# mapleCUx_large_401-014-not-produced.net
KiCad netlist of a schematic drawn in EAGLE
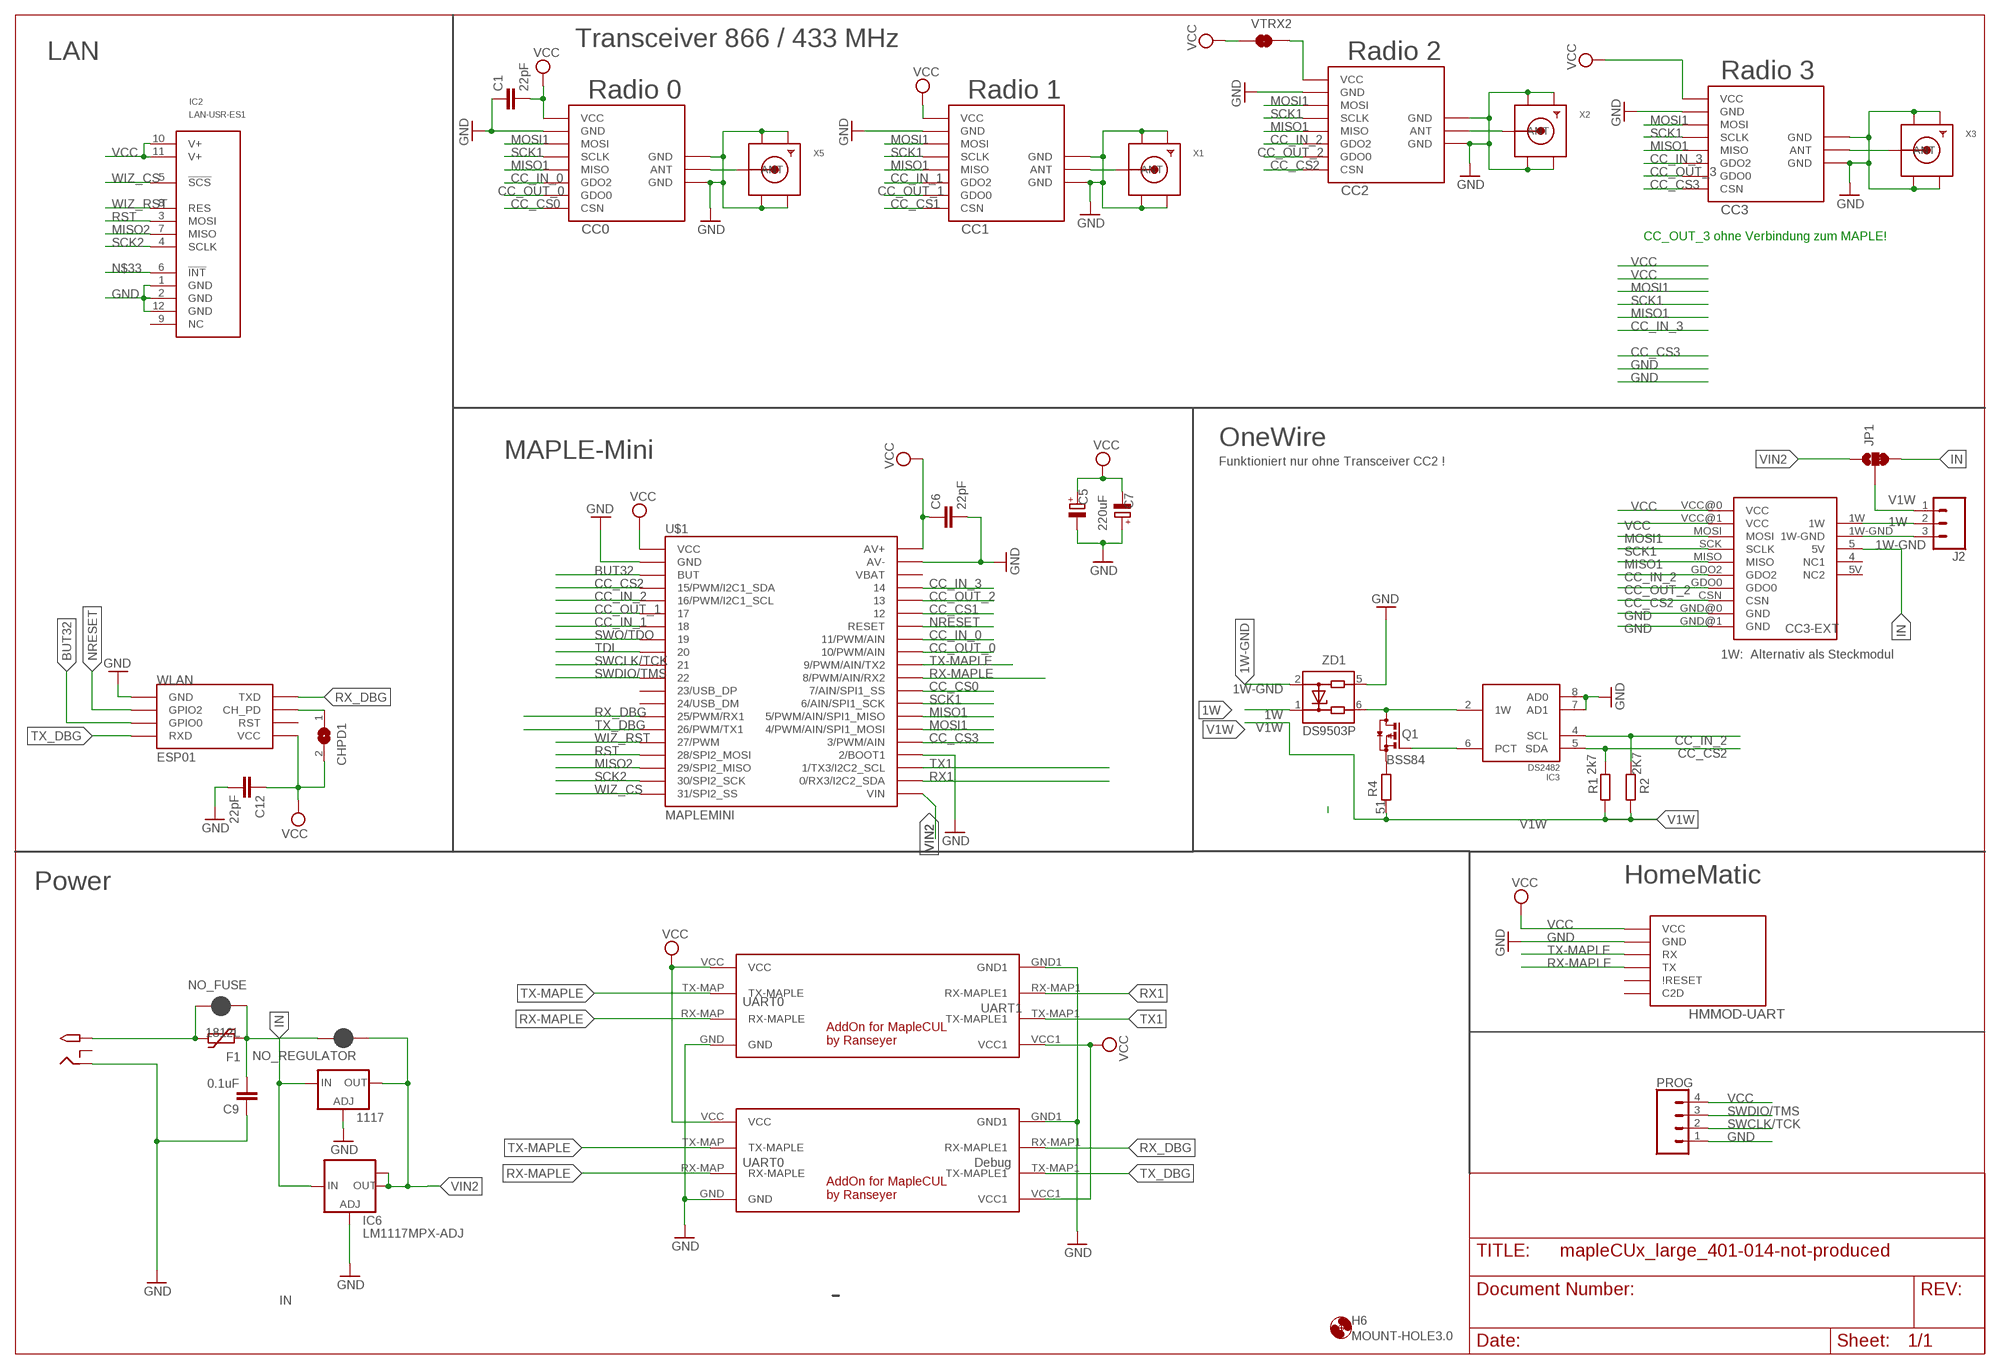
[diagram p0: schematic, sheet 1]

(export (version "E")
  (design (tool "Eeschema 10.0.6"))
  (components
    (comp (ref "1117")
      (value "LD117ADT50TR")
      (footprint "eagle-import:DPACK")
      (libsource (lib "eagle-import") (part "LD117A?DT50TR"))
    )
    (comp (ref "C1")
      (value "22pF")
      (footprint "eagle-import:C0805")
      (libsource (lib "eagle-import") (part "C-EUC0805"))
    )
    (comp (ref "C5")
      (value "220uF")
      (footprint "eagle-import:E5-8,5")
      (libsource (lib "eagle-import") (part "CPOL-EUE5-8.5"))
    )
    (comp (ref "C6")
      (value "22pF")
      (footprint "eagle-import:C0805")
      (libsource (lib "eagle-import") (part "C-EUC0805"))
    )
    (comp (ref "C7")
      (value "CPOL-EUSMCE")
      (footprint "eagle-import:SMC_E")
      (libsource (lib "eagle-import") (part "rcl_334_CPOL-EUSMCE"))
    )
    (comp (ref "C9")
      (value "0.1uF")
      (footprint "eagle-import:C1206")
      (libsource (lib "eagle-import") (part "C-EUC1206"))
    )
    (comp (ref "C12")
      (value "22pF")
      (footprint "eagle-import:C0805")
      (libsource (lib "eagle-import") (part "C-EUC0805"))
    )
    (comp (ref "CC0")
      (value "CC1101")
      (footprint "eagle-import:CC1101_MODULE1_SMD")
      (libsource (lib "eagle-import") (part "CC1101_MODULE1SMD"))
    )
    (comp (ref "CC1")
      (value "CC1101_MODULE1SMD")
      (footprint "eagle-import:CC1101_MODULE1_SMD")
      (libsource (lib "eagle-import") (part "CC1101_MODULE1SMD"))
    )
    (comp (ref "CC2")
      (value "CC1101_MODULE1SMD")
      (footprint "eagle-import:CC1101_MODULE1_SMD")
      (libsource (lib "eagle-import") (part "CC1101_MODULE1SMD"))
    )
    (comp (ref "CC3")
      (value "CC1101_MODULE1SMD")
      (footprint "eagle-import:CC1101_MODULE1_SMD")
      (libsource (lib "eagle-import") (part "CC1101_MODULE1SMD"))
    )
    (comp (ref "CC3-EXT")
      (value "ONEWIRE-MODULE")
      (footprint "eagle-import:ONEWIRE_CC1101_MODULE3_DIL")
      (libsource (lib "eagle-import") (part "ONEWIRE-MODULE"))
    )
    (comp (ref "CHPD1")
      (value "SJ")
      (footprint "eagle-import:SJ")
      (libsource (lib "eagle-import") (part "SJ"))
    )
    (comp (ref "F1")
      (value "1812L")
      (footprint "eagle-import:1812L")
      (libsource (lib "eagle-import") (part "1812L"))
    )
    (comp (ref "H6")
      (value "MOUNT-HOLE3.0")
      (footprint "eagle-import:3,0")
      (libsource (lib "eagle-import") (part "MOUNT-HOLE3.0"))
    )
    (comp (ref "HMMOD-UART")
      (value "HM-MOD-UARTDIL")
      (footprint "eagle-import:HM-MOD-UART-DIL")
      (libsource (lib "eagle-import") (part "HM-MOD-UARTDIL"))
    )
    (comp (ref "IC2")
      (value "LAN-USR-ES1")
      (footprint "eagle-import:USR-ES1")
      (libsource (lib "eagle-import") (part "LAN-USR-ES1"))
    )
    (comp (ref "IC3")
      (value "DS2482")
      (footprint "eagle-import:SO08")
      (libsource (lib "eagle-import") (part "DS2482-100S"))
    )
    (comp (ref "IC6")
      (value "LM1117MPX-ADJ")
      (footprint "eagle-import:SOT223")
      (libsource (lib "eagle-import") (part "LM1117MPX-ADJ"))
    )
    (comp (ref "J2")
      (value "CONN_03LONGPADS")
      (footprint "eagle-import:1X03_LONGPADS")
      (libsource (lib "eagle-import") (part "CONN_03LONGPADS"))
    )
    (comp (ref "JP1")
      (value "JUMPER-SMT_3_1-NC_TRACE_SILK")
      (footprint "eagle-import:SMT-JUMPER_3_1-NC_TRACE_SILK")
      (libsource (lib "eagle-import") (part "JUMPER-SMT_3_1-NC_TRACE_SILK"))
    )
    (comp (ref "NO_FUSE")
      (value "JUMPER-SMT_2_NC_PASTE_NO-SILK")
      (footprint "eagle-import:SMT-JUMPER_2_NC_PASTE_NO-SILK")
      (libsource (lib "eagle-import") (part "JUMPER-SMT_2_NC_PASTE_NO-SILK"))
    )
    (comp (ref "NO_REGULATOR")
      (value "JUMPER-SMT_2_NC_PASTE_NO-SILK")
      (footprint "eagle-import:SMT-JUMPER_2_NC_PASTE_NO-SILK")
      (libsource (lib "eagle-import") (part "JUMPER-SMT_2_NC_PASTE_NO-SILK"))
    )
    (comp (ref "PROG")
      (value "CONN_04LOCK")
      (footprint "eagle-import:1X04_LOCK")
      (libsource (lib "eagle-import") (part "CONN_04LOCK"))
    )
    (comp (ref "Q1")
      (value "BSS84")
      (footprint "eagle-import:SOT23")
      (libsource (lib "eagle-import") (part "BSS84"))
    )
    (comp (ref "R1")
      (value "2k7")
      (footprint "eagle-import:R0805")
      (libsource (lib "eagle-import") (part "R-EU_R0805"))
    )
    (comp (ref "R2")
      (value "2K7")
      (footprint "eagle-import:R0805")
      (libsource (lib "eagle-import") (part "R-EU_R0805"))
    )
    (comp (ref "R4")
      (value "51")
      (footprint "eagle-import:R0805")
      (libsource (lib "eagle-import") (part "R-EU_R0805"))
    )
    (comp (ref "U$1")
      (value "MAPLEMINI")
      (footprint "eagle-import:20-DIP")
      (libsource (lib "eagle-import") (part "MAPLEMINI"))
    )
    (comp (ref "U$2")
      (value "2.1MMJACKTHM")
      (footprint "eagle-import:PJ-102A")
      (libsource (lib "eagle-import") (part "2.1MMJACKTHM"))
    )
    (comp (ref "U$3")
      (value "MAPLE-CUL-ADDON-V01")
      (footprint "eagle-import:MAPLE-CUL-V01")
      (libsource (lib "eagle-import") (part "MAPLE-CUL-ADDON-V01"))
    )
    (comp (ref "U$4")
      (value "MAPLE-CUL-ADDON-V01")
      (footprint "eagle-import:MAPLE-CUL-V01")
      (libsource (lib "eagle-import") (part "MAPLE-CUL-ADDON-V01"))
    )
    (comp (ref "VTRX2")
      (value "JUMPER-SMT_2_NC_TRACE_SILK")
      (footprint "eagle-import:SMT-JUMPER_2_NC_TRACE_SILK")
      (libsource (lib "eagle-import") (part "JUMPER-SMT_2_NC_TRACE_SILK"))
    )
    (comp (ref "WLAN")
      (value "ESP01")
      (footprint "eagle-import:ESP01")
      (libsource (lib "eagle-import") (part "ESP01"))
    )
    (comp (ref "X1")
      (value "SMACONNECTOR_EDGE")
      (footprint "eagle-import:SMA_EDGELAUNCH")
      (libsource (lib "eagle-import") (part "SMACONNECTOR_EDGE"))
    )
    (comp (ref "X2")
      (value "SMACONNECTOR_EDGE")
      (footprint "eagle-import:SMA_EDGELAUNCH")
      (libsource (lib "eagle-import") (part "SMACONNECTOR_EDGE"))
    )
    (comp (ref "X3")
      (value "SMACONNECTOR_EDGE")
      (footprint "eagle-import:SMA_EDGELAUNCH")
      (libsource (lib "eagle-import") (part "SMACONNECTOR_EDGE"))
    )
    (comp (ref "X5")
      (value "SMACONNECTOR_EDGE")
      (footprint "eagle-import:SMA_EDGELAUNCH")
      (libsource (lib "eagle-import") (part "SMACONNECTOR_EDGE"))
    )
    (comp (ref "ZD1")
      (value "DS9503P")
      (footprint "eagle-import:TSOC6")
      (libsource (lib "eagle-import") (part "DS9503P"))
    )
  )
  (nets
    (net (code "1") (name "/CC_CS0") (class "Default")
      (node (ref "CC0") (pin "CSN") (pinfunction "CSN_CSN") (pintype "bidirectional"))
      (node (ref "U$1") (pin "29") (pinfunction "7/AIN/SPI1_SS_29") (pintype "bidirectional"))
    )
    (net (code "2") (name "/CC_CS1") (class "Default")
      (node (ref "CC1") (pin "CSN") (pinfunction "CSN_CSN") (pintype "bidirectional"))
      (node (ref "U$1") (pin "35") (pinfunction "12_35") (pintype "bidirectional"))
    )
    (net (code "3") (name "/CC_CS2") (class "Default")
      (node (ref "CC2") (pin "CSN") (pinfunction "CSN_CSN") (pintype "bidirectional"))
      (node (ref "CC3-EXT") (pin "CSN") (pinfunction "CSN_CSN") (pintype "bidirectional"))
      (node (ref "IC3") (pin "5") (pinfunction "SDA_5") (pintype "bidirectional"))
      (node (ref "R1") (pin "2") (pinfunction "2_2") (pintype "passive"))
      (node (ref "U$1") (pin "4") (pinfunction "15/PWM/I2C1_SDA_4") (pintype "bidirectional"))
    )
    (net (code "4") (name "/CC_CS3") (class "Default")
      (node (ref "CC3") (pin "CSN") (pinfunction "CSN_CSN") (pintype "bidirectional"))
      (node (ref "U$1") (pin "25") (pinfunction "3/PWM/AIN_25") (pintype "bidirectional"))
    )
    (net (code "5") (name "/CC_IN_0") (class "Default")
      (node (ref "CC0") (pin "GDO2") (pinfunction "GDO2_GDO2") (pintype "bidirectional"))
      (node (ref "U$1") (pin "33") (pinfunction "11/PWM/AIN_33") (pintype "bidirectional"))
    )
    (net (code "6") (name "/CC_IN_1") (class "Default")
      (node (ref "CC1") (pin "GDO2") (pinfunction "GDO2_GDO2") (pintype "bidirectional"))
      (node (ref "U$1") (pin "7") (pinfunction "18_7") (pintype "bidirectional"))
    )
    (net (code "7") (name "/CC_IN_2") (class "Default")
      (node (ref "CC2") (pin "GDO2") (pinfunction "GDO2_GDO2") (pintype "bidirectional"))
      (node (ref "CC3-EXT") (pin "GDO2") (pinfunction "GDO2_GDO2") (pintype "bidirectional"))
      (node (ref "IC3") (pin "4") (pinfunction "SCL_4") (pintype "input"))
      (node (ref "R2") (pin "2") (pinfunction "2_2") (pintype "passive"))
      (node (ref "U$1") (pin "5") (pinfunction "16/PWM/I2C1_SCL_5") (pintype "bidirectional"))
    )
    (net (code "8") (name "/CC_IN_3") (class "Default")
      (node (ref "CC3") (pin "GDO2") (pinfunction "GDO2_GDO2") (pintype "bidirectional"))
      (node (ref "U$1") (pin "37") (pinfunction "14_37") (pintype "bidirectional"))
    )
    (net (code "9") (name "/CC_OUT_0") (class "Default")
      (node (ref "CC0") (pin "GDO0") (pinfunction "GDO0_GDO0") (pintype "bidirectional"))
      (node (ref "U$1") (pin "32") (pinfunction "10/PWM/AIN_32") (pintype "bidirectional"))
    )
    (net (code "10") (name "/CC_OUT_1") (class "Default")
      (node (ref "CC1") (pin "GDO0") (pinfunction "GDO0_GDO0") (pintype "bidirectional"))
      (node (ref "U$1") (pin "6") (pinfunction "17_6") (pintype "bidirectional"))
    )
    (net (code "11") (name "/CC_OUT_2") (class "Default")
      (node (ref "CC2") (pin "GDO0") (pinfunction "GDO0_GDO0") (pintype "bidirectional"))
      (node (ref "CC3-EXT") (pin "GDO0") (pinfunction "GDO0_GDO0") (pintype "bidirectional"))
      (node (ref "U$1") (pin "36") (pinfunction "13_36") (pintype "bidirectional"))
    )
    (net (code "12") (name "/CC_OUT_3") (class "Default")
      (node (ref "CC3") (pin "GDO0") (pinfunction "GDO0_GDO0") (pintype "bidirectional"))
    )
    (net (code "13") (name "/MISO1") (class "Default")
      (node (ref "CC0") (pin "MISO") (pinfunction "MISO_MISO") (pintype "bidirectional"))
      (node (ref "CC1") (pin "MISO") (pinfunction "MISO_MISO") (pintype "bidirectional"))
      (node (ref "CC2") (pin "MISO") (pinfunction "MISO_MISO") (pintype "bidirectional"))
      (node (ref "CC3") (pin "MISO") (pinfunction "MISO_MISO") (pintype "bidirectional"))
      (node (ref "CC3-EXT") (pin "MISO") (pinfunction "MISO_MISO") (pintype "bidirectional"))
      (node (ref "U$1") (pin "27") (pinfunction "5/PWM/AIN/SPI1_MISO_27") (pintype "bidirectional"))
    )
    (net (code "14") (name "/MISO2") (class "Default")
      (node (ref "IC2") (pin "7") (pinfunction "MISO_7") (pintype "bidirectional"))
      (node (ref "U$1") (pin "18") (pinfunction "29/SPI2_MISO_18") (pintype "bidirectional"))
    )
    (net (code "15") (name "/MOSI1") (class "Default")
      (node (ref "CC0") (pin "MOSI") (pinfunction "MOSI_MOSI") (pintype "bidirectional"))
      (node (ref "CC1") (pin "MOSI") (pinfunction "MOSI_MOSI") (pintype "bidirectional"))
      (node (ref "CC2") (pin "MOSI") (pinfunction "MOSI_MOSI") (pintype "bidirectional"))
      (node (ref "CC3") (pin "MOSI") (pinfunction "MOSI_MOSI") (pintype "bidirectional"))
      (node (ref "CC3-EXT") (pin "MOSI") (pinfunction "MOSI_MOSI") (pintype "bidirectional"))
      (node (ref "U$1") (pin "26") (pinfunction "4/PWM/AIN/SPI1_MOSI_26") (pintype "bidirectional"))
    )
    (net (code "16") (name "/N$33") (class "Default")
      (node (ref "IC2") (pin "6") (pinfunction "~{INT}_6") (pintype "output"))
    )
    (net (code "17") (name "/RST") (class "Default")
      (node (ref "IC2") (pin "3") (pinfunction "MOSI_3") (pintype "bidirectional"))
      (node (ref "U$1") (pin "17") (pinfunction "28/SPI2_MOSI_17") (pintype "bidirectional"))
    )
    (net (code "18") (name "/SCK1") (class "Default")
      (node (ref "CC0") (pin "SCLK") (pinfunction "SCLK_SCLK") (pintype "bidirectional"))
      (node (ref "CC1") (pin "SCLK") (pinfunction "SCLK_SCLK") (pintype "bidirectional"))
      (node (ref "CC2") (pin "SCLK") (pinfunction "SCLK_SCLK") (pintype "bidirectional"))
      (node (ref "CC3") (pin "SCLK") (pinfunction "SCLK_SCLK") (pintype "bidirectional"))
      (node (ref "CC3-EXT") (pin "SCK") (pinfunction "SCLK_SCK") (pintype "bidirectional"))
      (node (ref "U$1") (pin "28") (pinfunction "6/AIN/SPI1_SCK_28") (pintype "bidirectional"))
    )
    (net (code "19") (name "/SCK2") (class "Default")
      (node (ref "IC2") (pin "4") (pinfunction "SCLK_4") (pintype "input"))
      (node (ref "U$1") (pin "19") (pinfunction "30/SPI2_SCK_19") (pintype "bidirectional"))
    )
    (net (code "20") (name "/SWCLK{slash}TCK") (class "Default")
      (node (ref "PROG") (pin "2") (pinfunction "2_2") (pintype "passive"))
      (node (ref "U$1") (pin "10") (pinfunction "21_10") (pintype "bidirectional"))
    )
    (net (code "21") (name "/SWDIO{slash}TMS") (class "Default")
      (node (ref "PROG") (pin "3") (pinfunction "3_3") (pintype "passive"))
      (node (ref "U$1") (pin "11") (pinfunction "22_11") (pintype "bidirectional"))
    )
    (net (code "22") (name "/SWO{slash}TDO") (class "Default")
      (node (ref "U$1") (pin "8") (pinfunction "19_8") (pintype "bidirectional"))
    )
    (net (code "23") (name "/TDI") (class "Default")
      (node (ref "U$1") (pin "9") (pinfunction "20_9") (pintype "bidirectional"))
    )
    (net (code "24") (name "/WIZ_CS") (class "Default")
      (node (ref "IC2") (pin "5") (pinfunction "~{SCS}_5") (pintype "input"))
      (node (ref "U$1") (pin "20") (pinfunction "31/SPI2_SS_20") (pintype "bidirectional"))
    )
    (net (code "25") (name "/WIZ_RST") (class "Default")
      (node (ref "IC2") (pin "8") (pinfunction "RES_8") (pintype "input"))
      (node (ref "U$1") (pin "16") (pinfunction "27/PWM_16") (pintype "bidirectional"))
    )
    (net (code "26") (name "1W") (class "Default")
      (node (ref "CC3-EXT") (pin "1W") (pinfunction "1W_1W") (pintype "bidirectional"))
      (node (ref "J2") (pin "2") (pinfunction "2_2") (pintype "passive"))
      (node (ref "ZD1") (pin "1") (pinfunction "P$1_1") (pintype "passive"))
    )
    (net (code "27") (name "1W-GND") (class "Default")
      (node (ref "CC3-EXT") (pin "1W-GND") (pinfunction "1W-GND_1W-GND") (pintype "bidirectional"))
      (node (ref "J2") (pin "3") (pinfunction "3_3") (pintype "passive"))
      (node (ref "ZD1") (pin "2") (pinfunction "P$2_2") (pintype "passive"))
    )
    (net (code "28") (name "BUT32") (class "Default")
      (node (ref "U$1") (pin "3") (pinfunction "BUT_3") (pintype "bidirectional"))
      (node (ref "WLAN") (pin "GPIO0") (pinfunction "GPIO0_GPIO0") (pintype "bidirectional"))
    )
    (net (code "29") (name "GND") (class "Default")
      (node (ref "1117") (pin "1") (pinfunction "ADJ_1") (pintype "input"))
      (node (ref "C1") (pin "1") (pinfunction "1_1") (pintype "passive"))
      (node (ref "C12") (pin "2") (pinfunction "2_2") (pintype "passive"))
      (node (ref "C5") (pin "-") (pinfunction "-_-") (pintype "passive"))
      (node (ref "C6") (pin "2") (pinfunction "2_2") (pintype "passive"))
      (node (ref "C7") (pin "+") (pinfunction "+_+") (pintype "passive"))
      (node (ref "C9") (pin "1") (pinfunction "1_1") (pintype "passive"))
      (node (ref "CC0") (pin "GND@0") (pinfunction "GND_GND@0") (pintype "power_in"))
      (node (ref "CC0") (pin "GND@1") (pinfunction "GND_GND@1") (pintype "power_in"))
      (node (ref "CC0") (pin "GND@2") (pinfunction "GND_GND@2") (pintype "power_in"))
      (node (ref "CC1") (pin "GND@0") (pinfunction "GND_GND@0") (pintype "power_in"))
      (node (ref "CC1") (pin "GND@1") (pinfunction "GND_GND@1") (pintype "power_in"))
      (node (ref "CC1") (pin "GND@2") (pinfunction "GND_GND@2") (pintype "power_in"))
      (node (ref "CC2") (pin "GND@0") (pinfunction "GND_GND@0") (pintype "power_in"))
      (node (ref "CC2") (pin "GND@1") (pinfunction "GND_GND@1") (pintype "power_in"))
      (node (ref "CC2") (pin "GND@2") (pinfunction "GND_GND@2") (pintype "power_in"))
      (node (ref "CC3") (pin "GND@0") (pinfunction "GND_GND@0") (pintype "power_in"))
      (node (ref "CC3") (pin "GND@1") (pinfunction "GND_GND@1") (pintype "power_in"))
      (node (ref "CC3") (pin "GND@2") (pinfunction "GND_GND@2") (pintype "power_in"))
      (node (ref "CC3-EXT") (pin "GND@0") (pinfunction "GND_GND@0") (pintype "power_in"))
      (node (ref "CC3-EXT") (pin "GND@1") (pinfunction "GND_GND@1") (pintype "power_in"))
      (node (ref "HMMOD-UART") (pin "2") (pinfunction "GND_2") (pintype "power_in"))
      (node (ref "IC2") (pin "1") (pinfunction "GND_1") (pintype "power_in"))
      (node (ref "IC2") (pin "12") (pinfunction "GND_12") (pintype "power_in"))
      (node (ref "IC2") (pin "2") (pinfunction "GND_2") (pintype "power_in"))
      (node (ref "IC3") (pin "7") (pinfunction "AD1_7") (pintype "input"))
      (node (ref "IC3") (pin "8") (pinfunction "AD0_8") (pintype "input"))
      (node (ref "IC6") (pin "1") (pinfunction "ADJ_1") (pintype "input"))
      (node (ref "PROG") (pin "1") (pinfunction "1_1") (pintype "passive"))
      (node (ref "U$1") (pin "2") (pinfunction "GND_2") (pintype "bidirectional"))
      (node (ref "U$1") (pin "24") (pinfunction "2/BOOT1_24") (pintype "bidirectional"))
      (node (ref "U$1") (pin "39") (pinfunction "AV-_39") (pintype "bidirectional"))
      (node (ref "U$2") (pin "RING") (pinfunction "RING_RING") (pintype "bidirectional"))
      (node (ref "U$3") (pin "GND") (pinfunction "GND_GND") (pintype "bidirectional"))
      (node (ref "U$3") (pin "GND1") (pinfunction "GND1_GND1") (pintype "bidirectional"))
      (node (ref "U$4") (pin "GND") (pinfunction "GND_GND") (pintype "bidirectional"))
      (node (ref "U$4") (pin "GND1") (pinfunction "GND1_GND1") (pintype "bidirectional"))
      (node (ref "WLAN") (pin "GND") (pinfunction "GND_GND") (pintype "bidirectional"))
      (node (ref "X1") (pin "GND@1") (pinfunction "GND4_GND@1") (pintype "power_in"))
      (node (ref "X1") (pin "GND@2") (pinfunction "GND3_GND@2") (pintype "power_in"))
      (node (ref "X1") (pin "GND@3") (pinfunction "GND2_GND@3") (pintype "power_in"))
      (node (ref "X1") (pin "GND@4") (pinfunction "GND1_GND@4") (pintype "power_in"))
      (node (ref "X2") (pin "GND@1") (pinfunction "GND4_GND@1") (pintype "power_in"))
      (node (ref "X2") (pin "GND@2") (pinfunction "GND3_GND@2") (pintype "power_in"))
      (node (ref "X2") (pin "GND@3") (pinfunction "GND2_GND@3") (pintype "power_in"))
      (node (ref "X2") (pin "GND@4") (pinfunction "GND1_GND@4") (pintype "power_in"))
      (node (ref "X3") (pin "GND@1") (pinfunction "GND4_GND@1") (pintype "power_in"))
      (node (ref "X3") (pin "GND@2") (pinfunction "GND3_GND@2") (pintype "power_in"))
      (node (ref "X3") (pin "GND@3") (pinfunction "GND2_GND@3") (pintype "power_in"))
      (node (ref "X3") (pin "GND@4") (pinfunction "GND1_GND@4") (pintype "power_in"))
      (node (ref "X5") (pin "GND@1") (pinfunction "GND4_GND@1") (pintype "power_in"))
      (node (ref "X5") (pin "GND@2") (pinfunction "GND3_GND@2") (pintype "power_in"))
      (node (ref "X5") (pin "GND@3") (pinfunction "GND2_GND@3") (pintype "power_in"))
      (node (ref "X5") (pin "GND@4") (pinfunction "GND1_GND@4") (pintype "power_in"))
      (node (ref "ZD1") (pin "5") (pinfunction "P$3_5") (pintype "passive"))
    )
    (net (code "30") (name "IN") (class "Default")
      (node (ref "1117") (pin "3") (pinfunction "IN_3") (pintype "input"))
      (node (ref "C9") (pin "2") (pinfunction "2_2") (pintype "passive"))
      (node (ref "CC3-EXT") (pin "5") (pinfunction "5V_5") (pintype "bidirectional"))
      (node (ref "F1") (pin "P$1") (pinfunction "1_P$1") (pintype "passive"))
      (node (ref "IC6") (pin "3") (pinfunction "IN_3") (pintype "input"))
      (node (ref "JP1") (pin "3") (pinfunction "3_3") (pintype "passive"))
      (node (ref "NO_FUSE") (pin "1") (pinfunction "1_1") (pintype "passive"))
      (node (ref "NO_REGULATOR") (pin "2") (pinfunction "2_2") (pintype "passive"))
    )
    (net (code "31") (name "NRESET") (class "Default")
      (node (ref "U$1") (pin "34") (pinfunction "RESET_34") (pintype "bidirectional"))
      (node (ref "WLAN") (pin "GPIO2") (pinfunction "GPIO2_GPIO2") (pintype "bidirectional"))
    )
    (net (code "32") (name "Net-(CC2-PadVCC)") (class "Default")
      (node (ref "CC2") (pin "VCC") (pinfunction "VCC_VCC") (pintype "power_in"))
      (node (ref "VTRX2") (pin "2") (pinfunction "2_2") (pintype "passive"))
    )
    (net (code "33") (name "Net-(CHPD1-Pad1)") (class "Default")
      (node (ref "CHPD1") (pin "1") (pinfunction "1_1") (pintype "passive"))
      (node (ref "WLAN") (pin "CH_PD") (pinfunction "CH_PD_CH_PD") (pintype "bidirectional"))
    )
    (net (code "34") (name "Net-(F1-2)") (class "Default")
      (node (ref "F1") (pin "P$2") (pinfunction "2_P$2") (pintype "passive"))
      (node (ref "NO_FUSE") (pin "2") (pinfunction "2_2") (pintype "passive"))
      (node (ref "U$2") (pin "TIP") (pinfunction "TIP_TIP") (pintype "bidirectional"))
    )
    (net (code "35") (name "Net-(IC3A-1W)") (class "Default")
      (node (ref "IC3") (pin "2") (pinfunction "1W_2") (pintype "open_collector"))
      (node (ref "Q1") (pin "3") (pinfunction "D_3") (pintype "passive"))
      (node (ref "ZD1") (pin "6") (pinfunction "P$4_6") (pintype "passive"))
    )
    (net (code "36") (name "Net-(IC3A-PCT)") (class "Default")
      (node (ref "IC3") (pin "6") (pinfunction "PCT_6") (pintype "output"))
      (node (ref "Q1") (pin "1") (pinfunction "G_1") (pintype "passive"))
    )
    (net (code "37") (name "Net-(Q1-S)") (class "Default")
      (node (ref "Q1") (pin "2") (pinfunction "S_2") (pintype "passive"))
      (node (ref "R4") (pin "1") (pinfunction "1_1") (pintype "passive"))
    )
    (net (code "38") (name "Net-(X1-ANT)") (class "Default")
      (node (ref "CC1") (pin "ANT") (pinfunction "ANT_ANT") (pintype "output"))
      (node (ref "X1") (pin "P") (pinfunction "ANT_P") (pintype "bidirectional"))
    )
    (net (code "39") (name "Net-(X2-ANT)") (class "Default")
      (node (ref "CC2") (pin "ANT") (pinfunction "ANT_ANT") (pintype "output"))
      (node (ref "X2") (pin "P") (pinfunction "ANT_P") (pintype "bidirectional"))
    )
    (net (code "40") (name "Net-(X3-ANT)") (class "Default")
      (node (ref "CC3") (pin "ANT") (pinfunction "ANT_ANT") (pintype "output"))
      (node (ref "X3") (pin "P") (pinfunction "ANT_P") (pintype "bidirectional"))
    )
    (net (code "41") (name "Net-(X5-ANT)") (class "Default")
      (node (ref "CC0") (pin "ANT") (pinfunction "ANT_ANT") (pintype "output"))
      (node (ref "X5") (pin "P") (pinfunction "ANT_P") (pintype "bidirectional"))
    )
    (net (code "42") (name "RX-MAPLE") (class "Default")
      (node (ref "HMMOD-UART") (pin "5") (pinfunction "TX_5") (pintype "bidirectional"))
      (node (ref "U$1") (pin "30") (pinfunction "8/PWM/AIN/RX2_30") (pintype "bidirectional"))
      (node (ref "U$3") (pin "RX-MAP") (pinfunction "RX-MAPLE_RX-MAP") (pintype "bidirectional"))
      (node (ref "U$4") (pin "RX-MAP") (pinfunction "RX-MAPLE_RX-MAP") (pintype "bidirectional"))
    )
    (net (code "43") (name "RX1") (class "Default")
      (node (ref "U$1") (pin "22") (pinfunction "0/RX3/I2C2_SDA_22") (pintype "bidirectional"))
      (node (ref "U$3") (pin "RX-MAP1") (pinfunction "RX-MAPLE1_RX-MAP1") (pintype "bidirectional"))
    )
    (net (code "44") (name "RX_DBG") (class "Default")
      (node (ref "U$1") (pin "14") (pinfunction "25/PWM/RX1_14") (pintype "bidirectional"))
      (node (ref "U$4") (pin "RX-MAP1") (pinfunction "RX-MAPLE1_RX-MAP1") (pintype "bidirectional"))
      (node (ref "WLAN") (pin "TX") (pinfunction "TXD_TX") (pintype "bidirectional"))
    )
    (net (code "45") (name "TX-MAPLE") (class "Default")
      (node (ref "HMMOD-UART") (pin "6") (pinfunction "RX_6") (pintype "bidirectional"))
      (node (ref "U$1") (pin "31") (pinfunction "9/PWM/AIN/TX2_31") (pintype "bidirectional"))
      (node (ref "U$3") (pin "TX-MAP") (pinfunction "TX-MAPLE_TX-MAP") (pintype "bidirectional"))
      (node (ref "U$4") (pin "TX-MAP") (pinfunction "TX-MAPLE_TX-MAP") (pintype "bidirectional"))
    )
    (net (code "46") (name "TX1") (class "Default")
      (node (ref "U$1") (pin "23") (pinfunction "1/TX3/I2C2_SCL_23") (pintype "bidirectional"))
      (node (ref "U$3") (pin "TX-MAP1") (pinfunction "TX-MAPLE1_TX-MAP1") (pintype "bidirectional"))
    )
    (net (code "47") (name "TX_DBG") (class "Default")
      (node (ref "U$1") (pin "15") (pinfunction "26/PWM/TX1_15") (pintype "bidirectional"))
      (node (ref "U$4") (pin "TX-MAP1") (pinfunction "TX-MAPLE1_TX-MAP1") (pintype "bidirectional"))
      (node (ref "WLAN") (pin "RX") (pinfunction "RXD_RX") (pintype "bidirectional"))
    )
    (net (code "48") (name "V1W") (class "Default")
      (node (ref "J2") (pin "1") (pinfunction "1_1") (pintype "passive"))
      (node (ref "JP1") (pin "2") (pinfunction "2_2") (pintype "passive"))
      (node (ref "R1") (pin "1") (pinfunction "1_1") (pintype "passive"))
      (node (ref "R2") (pin "1") (pinfunction "1_1") (pintype "passive"))
      (node (ref "R4") (pin "2") (pinfunction "2_2") (pintype "passive"))
    )
    (net (code "49") (name "VCC") (class "Default")
      (node (ref "C1") (pin "2") (pinfunction "2_2") (pintype "passive"))
      (node (ref "C12") (pin "1") (pinfunction "1_1") (pintype "passive"))
      (node (ref "C5") (pin "+") (pinfunction "+_+") (pintype "passive"))
      (node (ref "C6") (pin "1") (pinfunction "1_1") (pintype "passive"))
      (node (ref "C7") (pin "-") (pinfunction "-_-") (pintype "passive"))
      (node (ref "CC0") (pin "VCC") (pinfunction "VCC_VCC") (pintype "power_in"))
      (node (ref "CC1") (pin "VCC") (pinfunction "VCC_VCC") (pintype "power_in"))
      (node (ref "CC3") (pin "VCC") (pinfunction "VCC_VCC") (pintype "power_in"))
      (node (ref "CC3-EXT") (pin "VCC@0") (pinfunction "VCC_VCC@0") (pintype "power_in"))
      (node (ref "CC3-EXT") (pin "VCC@1") (pinfunction "VCC_VCC@1") (pintype "power_in"))
      (node (ref "CHPD1") (pin "2") (pinfunction "2_2") (pintype "passive"))
      (node (ref "HMMOD-UART") (pin "1") (pinfunction "VCC_1") (pintype "power_in"))
      (node (ref "IC2") (pin "10") (pinfunction "V+_10") (pintype "power_in"))
      (node (ref "IC2") (pin "11") (pinfunction "V+_11") (pintype "power_in"))
      (node (ref "PROG") (pin "4") (pinfunction "4_4") (pintype "passive"))
      (node (ref "U$1") (pin "1") (pinfunction "VCC_1") (pintype "bidirectional"))
      (node (ref "U$1") (pin "40") (pinfunction "AV+_40") (pintype "bidirectional"))
      (node (ref "U$3") (pin "VCC") (pinfunction "VCC_VCC") (pintype "bidirectional"))
      (node (ref "U$3") (pin "VCC1") (pinfunction "VCC1_VCC1") (pintype "bidirectional"))
      (node (ref "U$4") (pin "VCC") (pinfunction "VCC_VCC") (pintype "bidirectional"))
      (node (ref "U$4") (pin "VCC1") (pinfunction "VCC1_VCC1") (pintype "bidirectional"))
      (node (ref "VTRX2") (pin "1") (pinfunction "1_1") (pintype "passive"))
      (node (ref "WLAN") (pin "VCC") (pinfunction "VCC_VCC") (pintype "bidirectional"))
    )
    (net (code "50") (name "VIN2") (class "Default")
      (node (ref "1117") (pin "4") (pinfunction "OUT_4") (pintype "passive"))
      (node (ref "IC6") (pin "2") (pinfunction "OUT_2") (pintype "passive"))
      (node (ref "IC6") (pin "TAB") (pinfunction "OUT1_TAB") (pintype "passive"))
      (node (ref "JP1") (pin "1") (pinfunction "1_1") (pintype "passive"))
      (node (ref "NO_REGULATOR") (pin "1") (pinfunction "1_1") (pintype "passive"))
      (node (ref "U$1") (pin "21") (pinfunction "VIN_21") (pintype "bidirectional"))
    )
    (net (code "51") (name "unconnected-(CC3-EXT-NC1-Pad4)") (class "Default")
      (node (ref "CC3-EXT") (pin "4") (pinfunction "NC1_4") (pintype "bidirectional"))
    )
    (net (code "52") (name "unconnected-(CC3-EXT-NC2-Pad5V)") (class "Default")
      (node (ref "CC3-EXT") (pin "5V") (pinfunction "NC2_5V") (pintype "bidirectional"))
    )
    (net (code "53") (name "unconnected-(HMMOD-UART-C2D-Pad3)") (class "Default")
      (node (ref "HMMOD-UART") (pin "3") (pinfunction "C2D_3") (pintype "bidirectional"))
    )
    (net (code "54") (name "unconnected-(HMMOD-UART-\\~{RESET}-Pad4)") (class "Default")
      (node (ref "HMMOD-UART") (pin "4") (pinfunction "\\~{RESET}_4") (pintype "bidirectional"))
    )
    (net (code "55") (name "unconnected-(IC2-NC-Pad9)") (class "Default")
      (node (ref "IC2") (pin "9") (pinfunction "NC_9") (pintype "no_connect"))
    )
    (net (code "56") (name "unconnected-(U$1-23{slash}USB_DP-Pad12)") (class "Default")
      (node (ref "U$1") (pin "12") (pinfunction "23/USB_DP_12") (pintype "bidirectional"))
    )
    (net (code "57") (name "unconnected-(U$1-24{slash}USB_DM-Pad13)") (class "Default")
      (node (ref "U$1") (pin "13") (pinfunction "24/USB_DM_13") (pintype "bidirectional"))
    )
    (net (code "58") (name "unconnected-(U$1-VBAT-Pad38)") (class "Default")
      (node (ref "U$1") (pin "38") (pinfunction "VBAT_38") (pintype "bidirectional"))
    )
    (net (code "59") (name "unconnected-(U$2-PadRING_SW)") (class "Default")
      (node (ref "U$2") (pin "RING_SW") (pinfunction "RING_SW_RING_SW") (pintype "bidirectional"))
    )
    (net (code "60") (name "unconnected-(WLAN-PadRST)") (class "Default")
      (node (ref "WLAN") (pin "RST") (pinfunction "RST_RST") (pintype "bidirectional"))
    )
  )
)
